# LilyPad-Simple.net
KiCad netlist of a schematic drawn in EAGLE
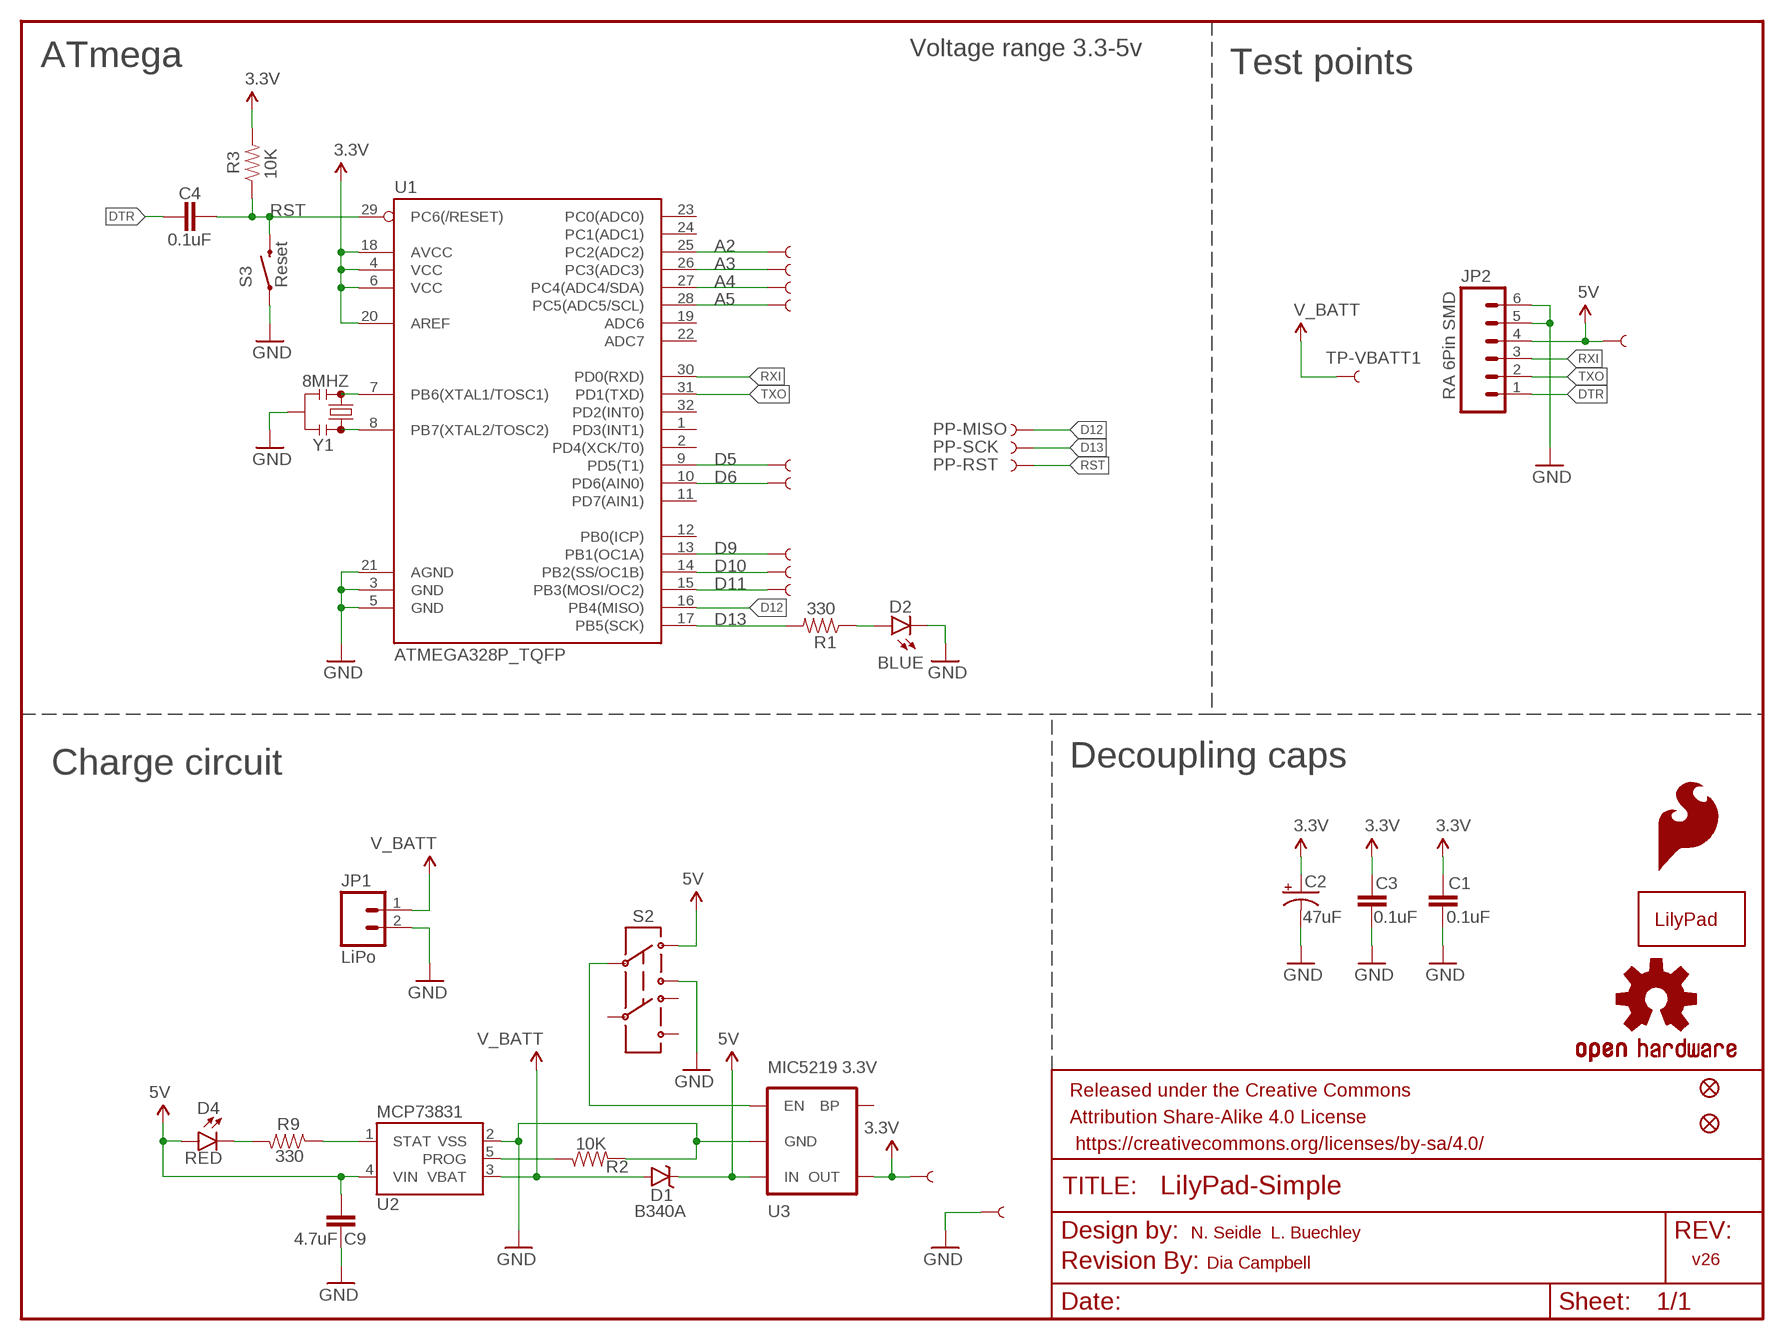
[diagram p0: schematic, sheet 1]

(export (version "E")
  (design (tool "Eeschema 10.0.6"))
  (components
    (comp (ref "A2/16")
      (value "SEWTAP9")
      (footprint "eagle-import:PETAL-LONG-1-2SIDE")
      (libsource (lib "eagle-import") (part "SEWTAP9"))
    )
    (comp (ref "A3/17")
      (value "SEWTAP9")
      (footprint "eagle-import:PETAL-LONG-1-2SIDE")
      (libsource (lib "eagle-import") (part "SEWTAP9"))
    )
    (comp (ref "A4/18")
      (value "SEWTAP9")
      (footprint "eagle-import:PETAL-LONG-1-2SIDE")
      (libsource (lib "eagle-import") (part "SEWTAP9"))
    )
    (comp (ref "A5/19")
      (value "SEWTAP9")
      (footprint "eagle-import:PETAL-LONG-1-2SIDE")
      (libsource (lib "eagle-import") (part "SEWTAP9"))
    )
    (comp (ref "C1")
      (value "0.1uF")
      (footprint "eagle-import:0603-CAP")
      (libsource (lib "eagle-import") (part "0.1UF-25V(+80/-20%)(0603)"))
    )
    (comp (ref "C2")
      (value "47uF")
      (footprint "eagle-import:EIA3528")
      (libsource (lib "eagle-import") (part "47UF-10V-10%(TANT)"))
    )
    (comp (ref "C3")
      (value "0.1uF")
      (footprint "eagle-import:0603-CAP")
      (libsource (lib "eagle-import") (part "0.1UF-25V(+80/-20%)(0603)"))
    )
    (comp (ref "C4")
      (value "0.1uF")
      (footprint "eagle-import:0603-CAP")
      (libsource (lib "eagle-import") (part "0.1UF-25V(+80/-20%)(0603)"))
    )
    (comp (ref "C9")
      (value "4.7uF")
      (footprint "eagle-import:0603-CAP")
      (libsource (lib "eagle-import") (part "4.7UF-6.3V-10%(0603)0603"))
    )
    (comp (ref "D1")
      (value "B340A")
      (footprint "eagle-import:SMA-DIODE")
      (libsource (lib "eagle-import") (part "DIODE-SCHOTTKY-B340A"))
    )
    (comp (ref "D2")
      (value "BLUE")
      (footprint "eagle-import:LED-0603")
      (libsource (lib "eagle-import") (part "LED-BLUE0603"))
    )
    (comp (ref "D4")
      (value "RED")
      (footprint "eagle-import:LED-0603")
      (libsource (lib "eagle-import") (part "LED-RED0603"))
    )
    (comp (ref "FID1")
      (value "FIDUCIAL1X2")
      (footprint "eagle-import:FIDUCIAL-1X2")
      (libsource (lib "eagle-import") (part "FIDUCIAL1X2"))
    )
    (comp (ref "FID2")
      (value "FIDUCIAL1X2")
      (footprint "eagle-import:FIDUCIAL-1X2")
      (libsource (lib "eagle-import") (part "FIDUCIAL1X2"))
    )
    (comp (ref "FRAME1")
      (value "FRAME-LETTER")
      (footprint "eagle-import:CREATIVE_COMMONS")
      (libsource (lib "eagle-import") (part "FRAME-LETTER"))
    )
    (comp (ref "JP1")
      (value "LiPo")
      (footprint "eagle-import:JST-2-SMD")
      (libsource (lib "eagle-import") (part "M02-JST-2MM-SMT"))
    )
    (comp (ref "JP2")
      (value "RA 6Pin SMD")
      (footprint "eagle-import:1X06-SMD")
      (libsource (lib "eagle-import") (part "M06SMD"))
    )
    (comp (ref "LOGO1")
      (value "OSHW-LOGOM-COPPER")
      (footprint "eagle-import:OSHW-LOGO-M_COPPER")
      (libsource (lib "eagle-import") (part "OSHW-LOGOM-COPPER"))
    )
    (comp (ref "LOGO2")
      (value "SFE_LOGO_FLAME.3COP")
      (footprint "eagle-import:SFE_LOGO_FLAME_COPPER_.3")
      (libsource (lib "eagle-import") (part "SFE_LOGO_FLAME.3COP"))
    )
    (comp (ref "PP-MISO")
      (value "TEST-POINT3X5")
      (footprint "eagle-import:PAD.03X.05")
      (libsource (lib "eagle-import") (part "TEST-POINT3X5"))
    )
    (comp (ref "PP-RST")
      (value "TEST-POINT3X5")
      (footprint "eagle-import:PAD.03X.05")
      (libsource (lib "eagle-import") (part "TEST-POINT3X5"))
    )
    (comp (ref "PP-SCK")
      (value "TEST-POINT3X5")
      (footprint "eagle-import:PAD.03X.05")
      (libsource (lib "eagle-import") (part "TEST-POINT3X5"))
    )
    (comp (ref "R1")
      (value "330")
      (footprint "eagle-import:0603-RES")
      (libsource (lib "eagle-import") (part "330OHM1/10W1%(0603)"))
    )
    (comp (ref "R2")
      (value "10K")
      (footprint "eagle-import:0603-RES")
      (libsource (lib "eagle-import") (part "10KOHM-1/10W-1%(0603)0603"))
    )
    (comp (ref "R3")
      (value "10K")
      (footprint "eagle-import:0603-RES")
      (libsource (lib "eagle-import") (part "10KOHM-1/10W-1%(0603)0603"))
    )
    (comp (ref "R9")
      (value "330")
      (footprint "eagle-import:0603-RES")
      (libsource (lib "eagle-import") (part "330OHM1/10W1%(0603)"))
    )
    (comp (ref "S2")
      (value "DPDT")
      (footprint "eagle-import:AYZ0202")
      (libsource (lib "eagle-import") (part "SWITCH-DPDTAYZ0202"))
    )
    (comp (ref "S3")
      (value "Reset")
      (footprint "eagle-import:TACTILE-SWITCH-SMD")
      (libsource (lib "eagle-import") (part "SWITCH-MOMENTARY-2SMD"))
    )
    (comp (ref "TP-FTDI_VCC")
      (value "TEST-POINT3X5")
      (footprint "eagle-import:PAD.03X.05")
      (libsource (lib "eagle-import") (part "TEST-POINT3X5"))
    )
    (comp (ref "TP-VBATT1")
      (value "TEST-POINT3X5")
      (footprint "eagle-import:PAD.03X.05")
      (libsource (lib "eagle-import") (part "TEST-POINT3X5"))
    )
    (comp (ref "U$1")
      (value "REVISION")
      (footprint "eagle-import:REVISION")
      (libsource (lib "eagle-import") (part "REVISION"))
    )
    (comp (ref "U$2")
      (value "LOGO-LPLPA")
      (footprint "eagle-import:LOGO-LPA")
      (libsource (lib "eagle-import") (part "LOGO-LPLPA"))
    )
    (comp (ref "U$4")
      (value "SEWTAP9")
      (footprint "eagle-import:PETAL-LONG-1-2SIDE")
      (libsource (lib "eagle-import") (part "SEWTAP9"))
    )
    (comp (ref "U$35")
      (value "SEWTAP9")
      (footprint "eagle-import:PETAL-LONG-1-2SIDE")
      (libsource (lib "eagle-import") (part "SEWTAP9"))
    )
    (comp (ref "U$37")
      (value "SEWTAP9")
      (footprint "eagle-import:PETAL-LONG-1-2SIDE")
      (libsource (lib "eagle-import") (part "SEWTAP9"))
    )
    (comp (ref "U$39")
      (value "SEWTAP9")
      (footprint "eagle-import:PETAL-LONG-1-2SIDE")
      (libsource (lib "eagle-import") (part "SEWTAP9"))
    )
    (comp (ref "U$41")
      (value "SEWTAP9")
      (footprint "eagle-import:PETAL-LONG-1-2SIDE")
      (libsource (lib "eagle-import") (part "SEWTAP9"))
    )
    (comp (ref "U$43")
      (value "SEWTAP9")
      (footprint "eagle-import:PETAL-LONG-1-2SIDE")
      (libsource (lib "eagle-import") (part "SEWTAP9"))
    )
    (comp (ref "U$45")
      (value "SEWTAP9")
      (footprint "eagle-import:PETAL-LONG-1-2SIDE")
      (libsource (lib "eagle-import") (part "SEWTAP9"))
    )
    (comp (ref "U1")
      (value "ATMEGA328P_TQFP")
      (footprint "eagle-import:TQFP32-08")
      (libsource (lib "eagle-import") (part "ATMEGA328P_TQFP"))
    )
    (comp (ref "U2")
      (value "MCP73831")
      (footprint "eagle-import:SOT23-5")
      (libsource (lib "eagle-import") (part "MCP73831"))
    )
    (comp (ref "U3")
      (value "MIC5219 3.3V")
      (footprint "eagle-import:SOT23-5")
      (libsource (lib "eagle-import") (part "V_REG_MIC52193.3V"))
    )
    (comp (ref "Y1")
      (value "8MHZ")
      (footprint "eagle-import:RESONATOR-SMD")
      (libsource (lib "eagle-import") (part "RESONATOR8MHZ"))
    )
  )
  (nets
    (net (code "1") (name "/A2") (class "Default")
      (node (ref "A2/16") (pin "1") (pinfunction "1_1") (pintype "bidirectional"))
      (node (ref "U1") (pin "25") (pinfunction "PC2(ADC2)_25") (pintype "bidirectional"))
    )
    (net (code "2") (name "/A3") (class "Default")
      (node (ref "A3/17") (pin "1") (pinfunction "1_1") (pintype "bidirectional"))
      (node (ref "U1") (pin "26") (pinfunction "PC3(ADC3)_26") (pintype "bidirectional"))
    )
    (net (code "3") (name "/A4") (class "Default")
      (node (ref "A4/18") (pin "1") (pinfunction "1_1") (pintype "bidirectional"))
      (node (ref "U1") (pin "27") (pinfunction "PC4(ADC4/SDA)_27") (pintype "bidirectional"))
    )
    (net (code "4") (name "/A5") (class "Default")
      (node (ref "A5/19") (pin "1") (pinfunction "1_1") (pintype "bidirectional"))
      (node (ref "U1") (pin "28") (pinfunction "PC5(ADC5/SCL)_28") (pintype "bidirectional"))
    )
    (net (code "5") (name "/D5") (class "Default")
      (node (ref "U$41") (pin "1") (pinfunction "1_1") (pintype "bidirectional"))
      (node (ref "U1") (pin "9") (pinfunction "PD5(T1)_9") (pintype "bidirectional"))
    )
    (net (code "6") (name "/D6") (class "Default")
      (node (ref "U$35") (pin "1") (pinfunction "1_1") (pintype "bidirectional"))
      (node (ref "U1") (pin "10") (pinfunction "PD6(AIN0)_10") (pintype "bidirectional"))
    )
    (net (code "7") (name "/D9") (class "Default")
      (node (ref "U$37") (pin "1") (pinfunction "1_1") (pintype "bidirectional"))
      (node (ref "U1") (pin "13") (pinfunction "PB1(OC1A)_13") (pintype "bidirectional"))
    )
    (net (code "8") (name "/D10") (class "Default")
      (node (ref "U$39") (pin "1") (pinfunction "1_1") (pintype "bidirectional"))
      (node (ref "U1") (pin "14") (pinfunction "PB2(SS/OC1B)_14") (pintype "bidirectional"))
    )
    (net (code "9") (name "/D11") (class "Default")
      (node (ref "U$4") (pin "1") (pinfunction "1_1") (pintype "bidirectional"))
      (node (ref "U1") (pin "15") (pinfunction "PB3(MOSI/OC2)_15") (pintype "bidirectional"))
    )
    (net (code "10") (name "3.3V") (class "Default")
      (node (ref "C1") (pin "1") (pinfunction "1_1") (pintype "passive"))
      (node (ref "C2") (pin "A") (pinfunction "+_A") (pintype "passive"))
      (node (ref "C3") (pin "1") (pinfunction "1_1") (pintype "passive"))
      (node (ref "R3") (pin "2") (pinfunction "2_2") (pintype "passive"))
      (node (ref "U$45") (pin "1") (pinfunction "1_1") (pintype "bidirectional"))
      (node (ref "U1") (pin "18") (pinfunction "AVCC_18") (pintype "bidirectional"))
      (node (ref "U1") (pin "20") (pinfunction "AREF_20") (pintype "bidirectional"))
      (node (ref "U1") (pin "4") (pinfunction "VCC_4") (pintype "bidirectional"))
      (node (ref "U1") (pin "6") (pinfunction "VCC_6") (pintype "bidirectional"))
      (node (ref "U3") (pin "5") (pinfunction "OUT_5") (pintype "passive"))
    )
    (net (code "11") (name "5V") (class "Default")
      (node (ref "C9") (pin "1") (pinfunction "1_1") (pintype "passive"))
      (node (ref "D1") (pin "C") (pinfunction "C_C") (pintype "passive"))
      (node (ref "D4") (pin "A") (pinfunction "A_A") (pintype "passive"))
      (node (ref "JP2") (pin "4") (pinfunction "4_4") (pintype "passive"))
      (node (ref "S2") (pin "1") (pinfunction "1_1") (pintype "bidirectional"))
      (node (ref "TP-FTDI_VCC") (pin "P$1") (pinfunction "1_P$1") (pintype "bidirectional"))
      (node (ref "U2") (pin "4") (pinfunction "VIN_4") (pintype "power_in"))
      (node (ref "U3") (pin "1") (pinfunction "IN_1") (pintype "input"))
    )
    (net (code "12") (name "D12") (class "Default")
      (node (ref "PP-MISO") (pin "P$1") (pinfunction "1_P$1") (pintype "bidirectional"))
      (node (ref "U1") (pin "16") (pinfunction "PB4(MISO)_16") (pintype "bidirectional"))
    )
    (net (code "13") (name "D13") (class "Default")
      (node (ref "PP-SCK") (pin "P$1") (pinfunction "1_P$1") (pintype "bidirectional"))
      (node (ref "R1") (pin "2") (pinfunction "2_2") (pintype "passive"))
      (node (ref "U1") (pin "17") (pinfunction "PB5(SCK)_17") (pintype "bidirectional"))
    )
    (net (code "14") (name "DTR") (class "Default")
      (node (ref "C4") (pin "1") (pinfunction "1_1") (pintype "passive"))
      (node (ref "JP2") (pin "1") (pinfunction "1_1") (pintype "passive"))
    )
    (net (code "15") (name "GND") (class "Default")
      (node (ref "C1") (pin "2") (pinfunction "2_2") (pintype "passive"))
      (node (ref "C2") (pin "C") (pinfunction "-_C") (pintype "passive"))
      (node (ref "C3") (pin "2") (pinfunction "2_2") (pintype "passive"))
      (node (ref "C9") (pin "2") (pinfunction "2_2") (pintype "passive"))
      (node (ref "D2") (pin "C") (pinfunction "C_C") (pintype "passive"))
      (node (ref "JP1") (pin "2") (pinfunction "1_2") (pintype "passive"))
      (node (ref "JP2") (pin "5") (pinfunction "5_5") (pintype "passive"))
      (node (ref "JP2") (pin "6") (pinfunction "6_6") (pintype "passive"))
      (node (ref "R2") (pin "2") (pinfunction "2_2") (pintype "passive"))
      (node (ref "S2") (pin "3") (pinfunction "3_3") (pintype "bidirectional"))
      (node (ref "S3") (pin "1") (pinfunction "1_1") (pintype "passive"))
      (node (ref "U$43") (pin "1") (pinfunction "1_1") (pintype "bidirectional"))
      (node (ref "U1") (pin "21") (pinfunction "AGND_21") (pintype "bidirectional"))
      (node (ref "U1") (pin "3") (pinfunction "GND_3") (pintype "bidirectional"))
      (node (ref "U1") (pin "5") (pinfunction "GND_5") (pintype "bidirectional"))
      (node (ref "U2") (pin "2") (pinfunction "VSS_2") (pintype "power_in"))
      (node (ref "U3") (pin "2") (pinfunction "GND_2") (pintype "input"))
      (node (ref "Y1") (pin "2") (pinfunction "2_2") (pintype "passive"))
    )
    (net (code "16") (name "Net-(D2-PadA)") (class "Default")
      (node (ref "D2") (pin "A") (pinfunction "A_A") (pintype "passive"))
      (node (ref "R1") (pin "1") (pinfunction "1_1") (pintype "passive"))
    )
    (net (code "17") (name "Net-(D4-PadC)") (class "Default")
      (node (ref "D4") (pin "C") (pinfunction "C_C") (pintype "passive"))
      (node (ref "R9") (pin "2") (pinfunction "2_2") (pintype "passive"))
    )
    (net (code "18") (name "Net-(U1-PB6(XTAL1{slash}TOSC1))") (class "Default")
      (node (ref "U1") (pin "7") (pinfunction "PB6(XTAL1/TOSC1)_7") (pintype "bidirectional"))
      (node (ref "Y1") (pin "1") (pinfunction "1_1") (pintype "passive"))
    )
    (net (code "19") (name "Net-(U1-PB7(XTAL2{slash}TOSC2))") (class "Default")
      (node (ref "U1") (pin "8") (pinfunction "PB7(XTAL2/TOSC2)_8") (pintype "bidirectional"))
      (node (ref "Y1") (pin "3") (pinfunction "3_3") (pintype "passive"))
    )
    (net (code "20") (name "Net-(U2-PROG)") (class "Default")
      (node (ref "R2") (pin "1") (pinfunction "1_1") (pintype "passive"))
      (node (ref "U2") (pin "5") (pinfunction "PROG_5") (pintype "input"))
    )
    (net (code "21") (name "Net-(U2-STAT)") (class "Default")
      (node (ref "R9") (pin "1") (pinfunction "1_1") (pintype "passive"))
      (node (ref "U2") (pin "1") (pinfunction "STAT_1") (pintype "output"))
    )
    (net (code "22") (name "Net-(U3-EN)") (class "Default")
      (node (ref "S2") (pin "2") (pinfunction "2_2") (pintype "bidirectional"))
      (node (ref "U3") (pin "3") (pinfunction "EN_3") (pintype "input"))
    )
    (net (code "23") (name "RST") (class "Default")
      (node (ref "C4") (pin "2") (pinfunction "2_2") (pintype "passive"))
      (node (ref "PP-RST") (pin "P$1") (pinfunction "1_P$1") (pintype "bidirectional"))
      (node (ref "R3") (pin "1") (pinfunction "1_1") (pintype "passive"))
      (node (ref "S3") (pin "3") (pinfunction "2_3") (pintype "passive"))
      (node (ref "U1") (pin "29") (pinfunction "PC6(/RESET)_29") (pintype "bidirectional"))
    )
    (net (code "24") (name "RXI") (class "Default")
      (node (ref "JP2") (pin "3") (pinfunction "3_3") (pintype "passive"))
      (node (ref "U1") (pin "30") (pinfunction "PD0(RXD)_30") (pintype "bidirectional"))
    )
    (net (code "25") (name "TXO") (class "Default")
      (node (ref "JP2") (pin "2") (pinfunction "2_2") (pintype "passive"))
      (node (ref "U1") (pin "31") (pinfunction "PD1(TXD)_31") (pintype "bidirectional"))
    )
    (net (code "26") (name "V_BATT") (class "Default")
      (node (ref "D1") (pin "A") (pinfunction "A_A") (pintype "passive"))
      (node (ref "JP1") (pin "1") (pinfunction "2_1") (pintype "passive"))
      (node (ref "TP-VBATT1") (pin "P$1") (pinfunction "1_P$1") (pintype "bidirectional"))
      (node (ref "U2") (pin "3") (pinfunction "VBAT_3") (pintype "power_in"))
    )
    (net (code "27") (name "unconnected-(S2-Pad4)") (class "Default")
      (node (ref "S2") (pin "4") (pinfunction "4_4") (pintype "bidirectional"))
    )
    (net (code "28") (name "unconnected-(S2-Pad5)") (class "Default")
      (node (ref "S2") (pin "5") (pinfunction "5_5") (pintype "bidirectional"))
    )
    (net (code "29") (name "unconnected-(S2-Pad6)") (class "Default")
      (node (ref "S2") (pin "6") (pinfunction "6_6") (pintype "bidirectional"))
    )
    (net (code "30") (name "unconnected-(U1-ADC6-Pad19)") (class "Default")
      (node (ref "U1") (pin "19") (pinfunction "ADC6_19") (pintype "bidirectional"))
    )
    (net (code "31") (name "unconnected-(U1-ADC7-Pad22)") (class "Default")
      (node (ref "U1") (pin "22") (pinfunction "ADC7_22") (pintype "bidirectional"))
    )
    (net (code "32") (name "unconnected-(U1-PB0(ICP)-Pad12)") (class "Default")
      (node (ref "U1") (pin "12") (pinfunction "PB0(ICP)_12") (pintype "bidirectional"))
    )
    (net (code "33") (name "unconnected-(U1-PC0(ADC0)-Pad23)") (class "Default")
      (node (ref "U1") (pin "23") (pinfunction "PC0(ADC0)_23") (pintype "bidirectional"))
    )
    (net (code "34") (name "unconnected-(U1-PC1(ADC1)-Pad24)") (class "Default")
      (node (ref "U1") (pin "24") (pinfunction "PC1(ADC1)_24") (pintype "bidirectional"))
    )
    (net (code "35") (name "unconnected-(U1-PD2(INT0)-Pad32)") (class "Default")
      (node (ref "U1") (pin "32") (pinfunction "PD2(INT0)_32") (pintype "bidirectional"))
    )
    (net (code "36") (name "unconnected-(U1-PD3(INT1)-Pad1)") (class "Default")
      (node (ref "U1") (pin "1") (pinfunction "PD3(INT1)_1") (pintype "bidirectional"))
    )
    (net (code "37") (name "unconnected-(U1-PD4(XCK{slash}T0)-Pad2)") (class "Default")
      (node (ref "U1") (pin "2") (pinfunction "PD4(XCK/T0)_2") (pintype "bidirectional"))
    )
    (net (code "38") (name "unconnected-(U1-PD7(AIN1)-Pad11)") (class "Default")
      (node (ref "U1") (pin "11") (pinfunction "PD7(AIN1)_11") (pintype "bidirectional"))
    )
    (net (code "39") (name "unconnected-(U3-BP-Pad4)") (class "Default")
      (node (ref "U3") (pin "4") (pinfunction "BP_4") (pintype "input"))
    )
  )
)
